# cpld_EPM3256_v3.net
KiCad netlist of a schematic drawn in EAGLE
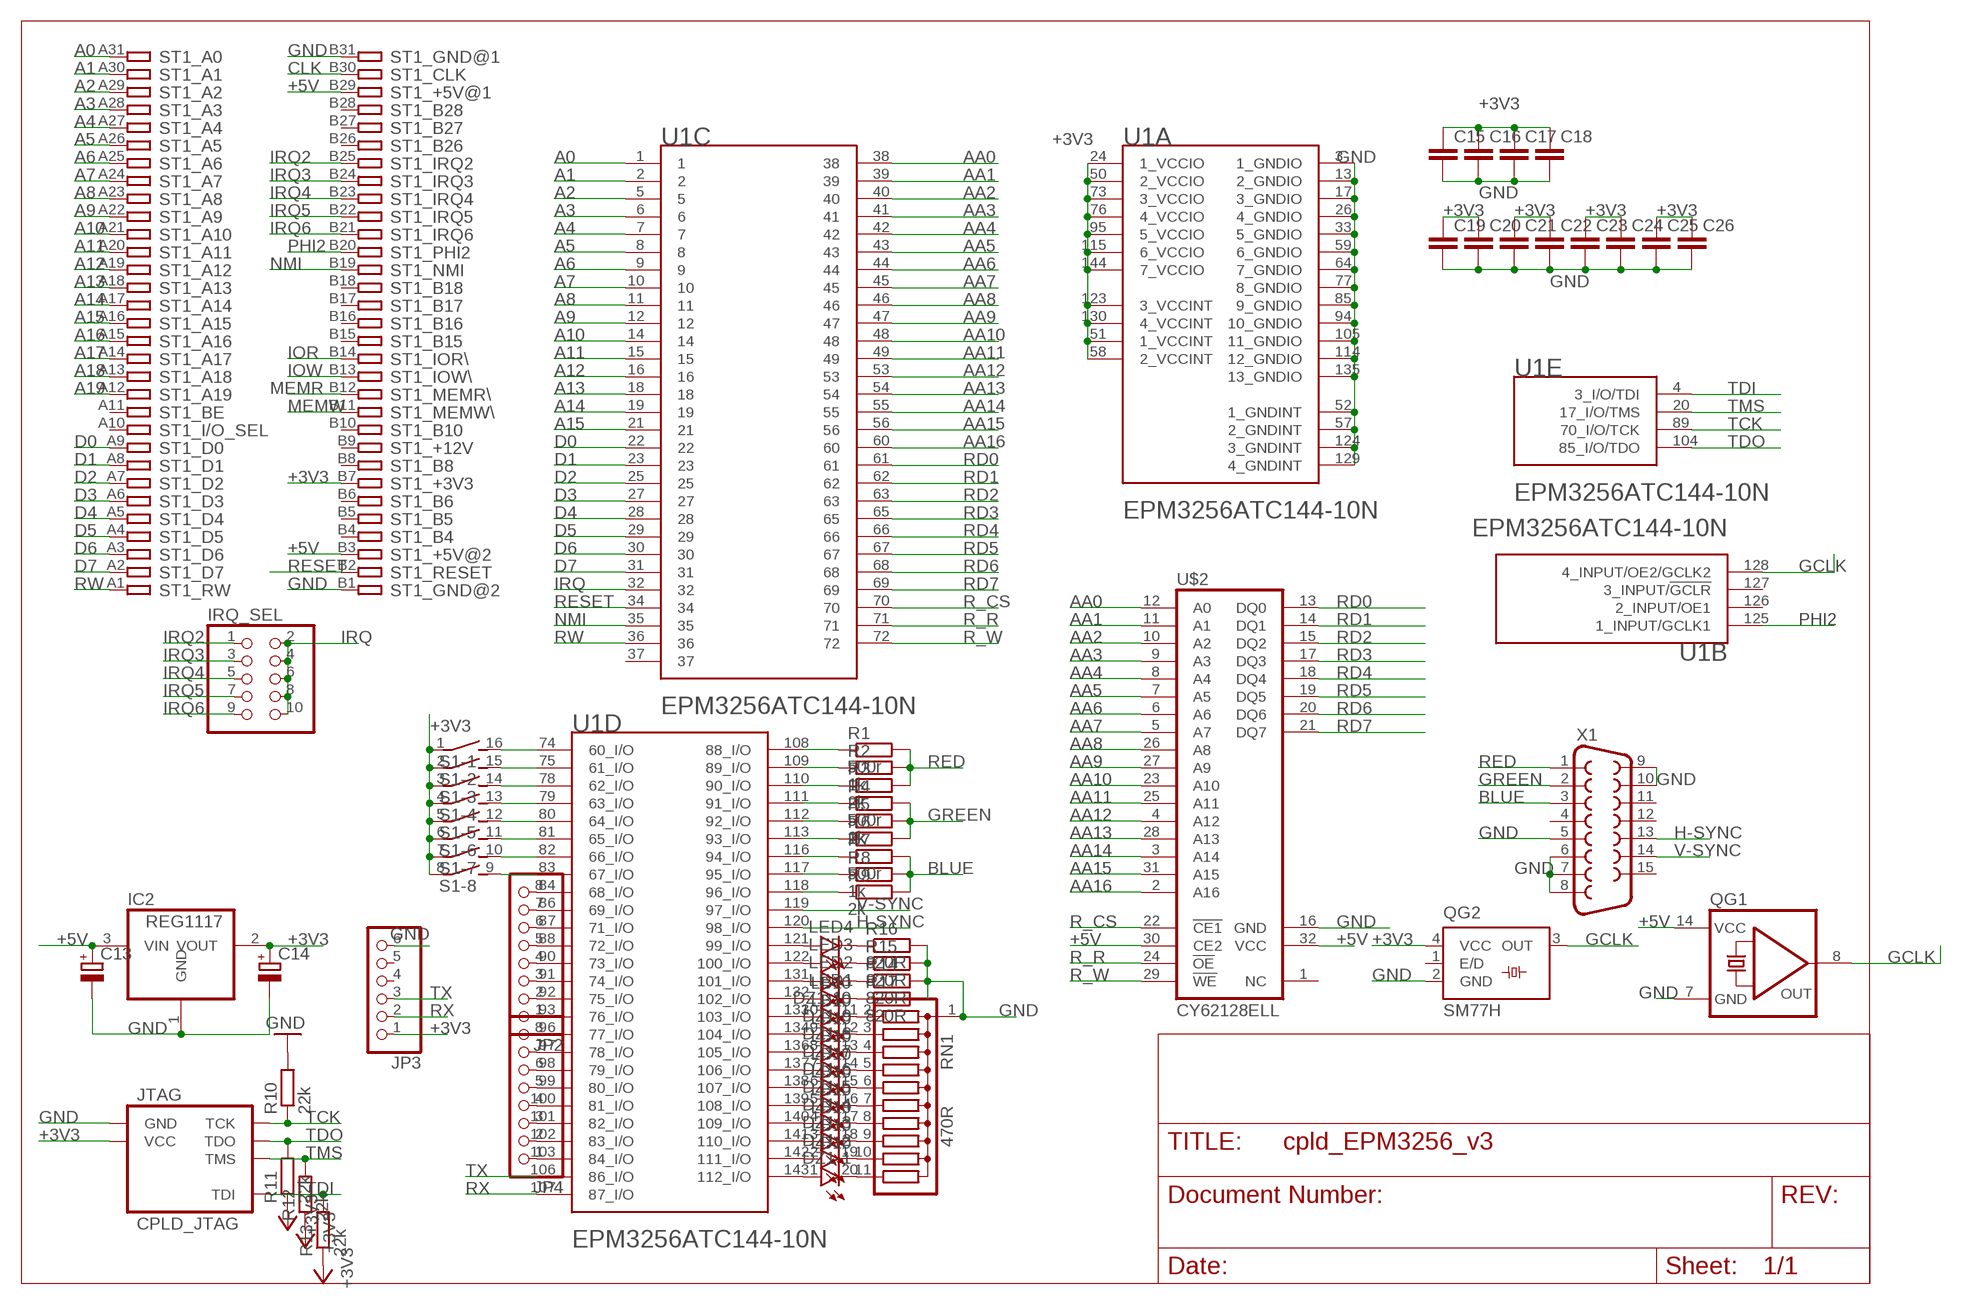
[diagram p0: schematic, sheet 1]

(export (version "E")
  (design (tool "Eeschema 10.0.6"))
  (components
    (comp (ref "C13")
      (value "CPOL-EUE2.5-5")
      (footprint "eagle-import:E2,5-5")
      (libsource (lib "eagle-import") (part "CPOL-EUE2.5-5"))
    )
    (comp (ref "C14")
      (value "CPOL-EUE2.5-5")
      (footprint "eagle-import:E2,5-5")
      (libsource (lib "eagle-import") (part "CPOL-EUE2.5-5"))
    )
    (comp (ref "C15")
      (value "C-EU050-035X075")
      (footprint "eagle-import:C050-035X075")
      (libsource (lib "eagle-import") (part "C-EU050-035X075"))
    )
    (comp (ref "C16")
      (value "C-EU050-035X075")
      (footprint "eagle-import:C050-035X075")
      (libsource (lib "eagle-import") (part "C-EU050-035X075"))
    )
    (comp (ref "C17")
      (value "C-EU050-035X075")
      (footprint "eagle-import:C050-035X075")
      (libsource (lib "eagle-import") (part "C-EU050-035X075"))
    )
    (comp (ref "C18")
      (value "C-EU050-035X075")
      (footprint "eagle-import:C050-035X075")
      (libsource (lib "eagle-import") (part "C-EU050-035X075"))
    )
    (comp (ref "C19")
      (value "C-EU050-035X075")
      (footprint "eagle-import:C050-035X075")
      (libsource (lib "eagle-import") (part "C-EU050-035X075"))
    )
    (comp (ref "C20")
      (value "C-EU050-035X075")
      (footprint "eagle-import:C050-035X075")
      (libsource (lib "eagle-import") (part "C-EU050-035X075"))
    )
    (comp (ref "C21")
      (value "C-EU050-035X075")
      (footprint "eagle-import:C050-035X075")
      (libsource (lib "eagle-import") (part "C-EU050-035X075"))
    )
    (comp (ref "C22")
      (value "C-EU050-035X075")
      (footprint "eagle-import:C050-035X075")
      (libsource (lib "eagle-import") (part "C-EU050-035X075"))
    )
    (comp (ref "C23")
      (value "C-EU050-035X075")
      (footprint "eagle-import:C050-035X075")
      (libsource (lib "eagle-import") (part "C-EU050-035X075"))
    )
    (comp (ref "C24")
      (value "C-EU050-035X075")
      (footprint "eagle-import:C050-035X075")
      (libsource (lib "eagle-import") (part "C-EU050-035X075"))
    )
    (comp (ref "C25")
      (value "C-EU050-035X075")
      (footprint "eagle-import:C050-035X075")
      (libsource (lib "eagle-import") (part "C-EU050-035X075"))
    )
    (comp (ref "C26")
      (value "C-EU050-035X075")
      (footprint "eagle-import:C050-035X075")
      (libsource (lib "eagle-import") (part "C-EU050-035X075"))
    )
    (comp (ref "DZ1")
      (value "LB10")
      (footprint "eagle-import:LB10")
      (libsource (lib "eagle-import") (part "LB10"))
    )
    (comp (ref "IC2")
      (value "REG1117")
      (footprint "eagle-import:SOT223")
      (libsource (lib "eagle-import") (part "REG1117"))
    )
    (comp (ref "IRQ_SEL")
      (value "PINHD-2X5")
      (footprint "eagle-import:2X05")
      (libsource (lib "eagle-import") (part "PINHD-2X5"))
    )
    (comp (ref "JP2")
      (value "PINHD-1X8")
      (footprint "eagle-import:1X08")
      (libsource (lib "eagle-import") (part "PINHD-1X8"))
    )
    (comp (ref "JP3")
      (value "PINHD-1X6/90")
      (footprint "eagle-import:1X06_90")
      (libsource (lib "eagle-import") (part "PINHD-1X6/90"))
    )
    (comp (ref "JP4")
      (value "PINHD-1X8")
      (footprint "eagle-import:1X08")
      (libsource (lib "eagle-import") (part "PINHD-1X8"))
    )
    (comp (ref "JTAG")
      (value "CPLD_JTAG")
      (footprint "eagle-import:2X05")
      (libsource (lib "eagle-import") (part "CPLD_JTAG"))
    )
    (comp (ref "LED1")
      (value "LED3MM")
      (footprint "eagle-import:LED3MM")
      (libsource (lib "eagle-import") (part "LED3MM"))
    )
    (comp (ref "LED2")
      (value "LED3MM")
      (footprint "eagle-import:LED3MM")
      (libsource (lib "eagle-import") (part "LED3MM"))
    )
    (comp (ref "LED3")
      (value "LED3MM")
      (footprint "eagle-import:LED3MM")
      (libsource (lib "eagle-import") (part "LED3MM"))
    )
    (comp (ref "LED4")
      (value "LED3MM")
      (footprint "eagle-import:LED3MM")
      (libsource (lib "eagle-import") (part "LED3MM"))
    )
    (comp (ref "QG1")
      (value "QG5860")
      (footprint "eagle-import:DIL14S")
      (libsource (lib "eagle-import") (part "QG5860"))
    )
    (comp (ref "QG2")
      (value "SM77H")
      (footprint "eagle-import:SM77H")
      (libsource (lib "eagle-import") (part "SM77H"))
    )
    (comp (ref "R1")
      (value "500r")
      (footprint "eagle-import:0204V")
      (libsource (lib "eagle-import") (part "R-EU_0204/2V"))
    )
    (comp (ref "R2")
      (value "1k")
      (footprint "eagle-import:0204V")
      (libsource (lib "eagle-import") (part "R-EU_0204/2V"))
    )
    (comp (ref "R3")
      (value "2k")
      (footprint "eagle-import:0204V")
      (libsource (lib "eagle-import") (part "R-EU_0204/2V"))
    )
    (comp (ref "R4")
      (value "500r")
      (footprint "eagle-import:0204V")
      (libsource (lib "eagle-import") (part "R-EU_0204/2V"))
    )
    (comp (ref "R5")
      (value "1k")
      (footprint "eagle-import:0204V")
      (libsource (lib "eagle-import") (part "R-EU_0204/2V"))
    )
    (comp (ref "R6")
      (value "2k")
      (footprint "eagle-import:0204V")
      (libsource (lib "eagle-import") (part "R-EU_0204/2V"))
    )
    (comp (ref "R7")
      (value "500r")
      (footprint "eagle-import:0204V")
      (libsource (lib "eagle-import") (part "R-EU_0204/2V"))
    )
    (comp (ref "R8")
      (value "1k")
      (footprint "eagle-import:0204V")
      (libsource (lib "eagle-import") (part "R-EU_0204/2V"))
    )
    (comp (ref "R9")
      (value "2k")
      (footprint "eagle-import:0204V")
      (libsource (lib "eagle-import") (part "R-EU_0204/2V"))
    )
    (comp (ref "R10")
      (value "22k")
      (footprint "eagle-import:0207_7")
      (libsource (lib "eagle-import") (part "R-EU_0207/7"))
    )
    (comp (ref "R11")
      (value "22k")
      (footprint "eagle-import:0207_7")
      (libsource (lib "eagle-import") (part "R-EU_0207/7"))
    )
    (comp (ref "R12")
      (value "22k")
      (footprint "eagle-import:0207_7")
      (libsource (lib "eagle-import") (part "R-EU_0207/7"))
    )
    (comp (ref "R13")
      (value "22k")
      (footprint "eagle-import:0207_7")
      (libsource (lib "eagle-import") (part "R-EU_0207/7"))
    )
    (comp (ref "R14")
      (value "820R")
      (footprint "eagle-import:0207_2V")
      (libsource (lib "eagle-import") (part "R-EU_0207/2V"))
    )
    (comp (ref "R15")
      (value "820R")
      (footprint "eagle-import:0207_2V")
      (libsource (lib "eagle-import") (part "R-EU_0207/2V"))
    )
    (comp (ref "R16")
      (value "820R")
      (footprint "eagle-import:0207_2V")
      (libsource (lib "eagle-import") (part "R-EU_0207/2V"))
    )
    (comp (ref "R17")
      (value "820R")
      (footprint "eagle-import:0207_2V")
      (libsource (lib "eagle-import") (part "R-EU_0207/2V"))
    )
    (comp (ref "RN1")
      (value "470R")
      (footprint "eagle-import:SIL11")
      (libsource (lib "eagle-import") (part "G10R"))
    )
    (comp (ref "S1")
      (value "DIP08S")
      (footprint "eagle-import:DIP08S")
      (libsource (lib "eagle-import") (part "DIP08S"))
    )
    (comp (ref "ST1")
      (value "IBM8BIT_ISA")
      (footprint "eagle-import:IBM8BIT")
      (libsource (lib "eagle-import") (part "IBM8BIT_ISA"))
    )
    (comp (ref "U$2")
      (value "CY62128ELL")
      (footprint "eagle-import:SOIC32")
      (libsource (lib "eagle-import") (part "CY62128ELL"))
    )
    (comp (ref "U1")
      (value "EPM3256ATC144")
      (footprint "eagle-import:TQFP144-BB")
      (libsource (lib "eagle-import") (part "EPM3256ATC144"))
    )
    (comp (ref "X1")
      (value "F15HDH")
      (footprint "eagle-import:HDF15H")
      (libsource (lib "eagle-import") (part "F15HDH"))
    )
  )
  (nets
    (net (code "1") (name "+3V3") (class "Default")
      (node (ref "C14") (pin "+") (pinfunction "+_+") (pintype "passive"))
      (node (ref "C15") (pin "1") (pinfunction "1_1") (pintype "passive"))
      (node (ref "C16") (pin "1") (pinfunction "1_1") (pintype "passive"))
      (node (ref "C17") (pin "1") (pinfunction "1_1") (pintype "passive"))
      (node (ref "C18") (pin "1") (pinfunction "1_1") (pintype "passive"))
      (node (ref "C19") (pin "1") (pinfunction "1_1") (pintype "passive"))
      (node (ref "C20") (pin "1") (pinfunction "1_1") (pintype "passive"))
      (node (ref "C21") (pin "1") (pinfunction "1_1") (pintype "passive"))
      (node (ref "C22") (pin "1") (pinfunction "1_1") (pintype "passive"))
      (node (ref "C23") (pin "1") (pinfunction "1_1") (pintype "passive"))
      (node (ref "C24") (pin "1") (pinfunction "1_1") (pintype "passive"))
      (node (ref "C25") (pin "1") (pinfunction "1_1") (pintype "passive"))
      (node (ref "C26") (pin "1") (pinfunction "1_1") (pintype "passive"))
      (node (ref "IC2") (pin "2") (pinfunction "VOUT_2") (pintype "output"))
      (node (ref "JP3") (pin "1") (pinfunction "1_1") (pintype "passive"))
      (node (ref "JTAG") (pin "4") (pinfunction "VCC_4") (pintype "power_in"))
      (node (ref "QG2") (pin "4") (pinfunction "VCC_4") (pintype "power_in"))
      (node (ref "R11") (pin "1") (pinfunction "1_1") (pintype "passive"))
      (node (ref "R12") (pin "1") (pinfunction "1_1") (pintype "passive"))
      (node (ref "R13") (pin "1") (pinfunction "1_1") (pintype "passive"))
      (node (ref "S1") (pin "1") (pinfunction "1_1") (pintype "passive"))
      (node (ref "S1") (pin "2") (pinfunction "1_2") (pintype "passive"))
      (node (ref "S1") (pin "3") (pinfunction "1_3") (pintype "passive"))
      (node (ref "S1") (pin "4") (pinfunction "1_4") (pintype "passive"))
      (node (ref "S1") (pin "5") (pinfunction "1_5") (pintype "passive"))
      (node (ref "S1") (pin "6") (pinfunction "1_6") (pintype "passive"))
      (node (ref "S1") (pin "7") (pinfunction "1_7") (pintype "passive"))
      (node (ref "S1") (pin "8") (pinfunction "1_8") (pintype "passive"))
      (node (ref "ST1") (pin "B7") (pinfunction "P_B7") (pintype "bidirectional"))
      (node (ref "U1") (pin "115") (pinfunction "6_VCCIO_115") (pintype "power_in"))
      (node (ref "U1") (pin "123") (pinfunction "3_VCCINT_123") (pintype "power_in"))
      (node (ref "U1") (pin "130") (pinfunction "4_VCCINT_130") (pintype "power_in"))
      (node (ref "U1") (pin "144") (pinfunction "7_VCCIO_144") (pintype "power_in"))
      (node (ref "U1") (pin "24") (pinfunction "1_VCCIO_24") (pintype "power_in"))
      (node (ref "U1") (pin "50") (pinfunction "2_VCCIO_50") (pintype "power_in"))
      (node (ref "U1") (pin "51") (pinfunction "1_VCCINT_51") (pintype "power_in"))
      (node (ref "U1") (pin "58") (pinfunction "2_VCCINT_58") (pintype "power_in"))
      (node (ref "U1") (pin "73") (pinfunction "3_VCCIO_73") (pintype "power_in"))
      (node (ref "U1") (pin "76") (pinfunction "4_VCCIO_76") (pintype "power_in"))
      (node (ref "U1") (pin "95") (pinfunction "5_VCCIO_95") (pintype "power_in"))
    )
    (net (code "2") (name "/+5V") (class "Default")
      (node (ref "C13") (pin "+") (pinfunction "+_+") (pintype "passive"))
      (node (ref "IC2") (pin "3") (pinfunction "VIN_3") (pintype "input"))
      (node (ref "QG1") (pin "14") (pinfunction "VCC_14") (pintype "power_in"))
      (node (ref "ST1") (pin "B29") (pinfunction "P_B29") (pintype "bidirectional"))
      (node (ref "ST1") (pin "B3") (pinfunction "P_B3") (pintype "bidirectional"))
      (node (ref "U$2") (pin "30") (pinfunction "CE2_30") (pintype "input"))
      (node (ref "U$2") (pin "32") (pinfunction "VCC_32") (pintype "bidirectional"))
    )
    (net (code "3") (name "/A0") (class "Default")
      (node (ref "ST1") (pin "A31") (pinfunction "P_A31") (pintype "bidirectional"))
      (node (ref "U1") (pin "1") (pinfunction "1_1") (pintype "bidirectional"))
    )
    (net (code "4") (name "/A1") (class "Default")
      (node (ref "ST1") (pin "A30") (pinfunction "P_A30") (pintype "bidirectional"))
      (node (ref "U1") (pin "2") (pinfunction "2_2") (pintype "bidirectional"))
    )
    (net (code "5") (name "/A2") (class "Default")
      (node (ref "ST1") (pin "A29") (pinfunction "P_A29") (pintype "bidirectional"))
      (node (ref "U1") (pin "5") (pinfunction "5_5") (pintype "bidirectional"))
    )
    (net (code "6") (name "/A3") (class "Default")
      (node (ref "ST1") (pin "A28") (pinfunction "P_A28") (pintype "bidirectional"))
      (node (ref "U1") (pin "6") (pinfunction "6_6") (pintype "bidirectional"))
    )
    (net (code "7") (name "/A4") (class "Default")
      (node (ref "ST1") (pin "A27") (pinfunction "P_A27") (pintype "bidirectional"))
      (node (ref "U1") (pin "7") (pinfunction "7_7") (pintype "bidirectional"))
    )
    (net (code "8") (name "/A5") (class "Default")
      (node (ref "ST1") (pin "A26") (pinfunction "P_A26") (pintype "bidirectional"))
      (node (ref "U1") (pin "8") (pinfunction "8_8") (pintype "bidirectional"))
    )
    (net (code "9") (name "/A6") (class "Default")
      (node (ref "ST1") (pin "A25") (pinfunction "P_A25") (pintype "bidirectional"))
      (node (ref "U1") (pin "9") (pinfunction "9_9") (pintype "bidirectional"))
    )
    (net (code "10") (name "/A7") (class "Default")
      (node (ref "ST1") (pin "A24") (pinfunction "P_A24") (pintype "bidirectional"))
      (node (ref "U1") (pin "10") (pinfunction "10_10") (pintype "bidirectional"))
    )
    (net (code "11") (name "/A8") (class "Default")
      (node (ref "ST1") (pin "A23") (pinfunction "P_A23") (pintype "bidirectional"))
      (node (ref "U1") (pin "11") (pinfunction "11_11") (pintype "bidirectional"))
    )
    (net (code "12") (name "/A9") (class "Default")
      (node (ref "ST1") (pin "A22") (pinfunction "P_A22") (pintype "bidirectional"))
      (node (ref "U1") (pin "12") (pinfunction "12_12") (pintype "bidirectional"))
    )
    (net (code "13") (name "/A10") (class "Default")
      (node (ref "ST1") (pin "A21") (pinfunction "P_A21") (pintype "bidirectional"))
      (node (ref "U1") (pin "14") (pinfunction "14_14") (pintype "bidirectional"))
    )
    (net (code "14") (name "/A11") (class "Default")
      (node (ref "ST1") (pin "A20") (pinfunction "P_A20") (pintype "bidirectional"))
      (node (ref "U1") (pin "15") (pinfunction "15_15") (pintype "bidirectional"))
    )
    (net (code "15") (name "/A12") (class "Default")
      (node (ref "ST1") (pin "A19") (pinfunction "P_A19") (pintype "bidirectional"))
      (node (ref "U1") (pin "16") (pinfunction "16_16") (pintype "bidirectional"))
    )
    (net (code "16") (name "/A13") (class "Default")
      (node (ref "ST1") (pin "A18") (pinfunction "P_A18") (pintype "bidirectional"))
      (node (ref "U1") (pin "18") (pinfunction "18_18") (pintype "bidirectional"))
    )
    (net (code "17") (name "/A14") (class "Default")
      (node (ref "ST1") (pin "A17") (pinfunction "P_A17") (pintype "bidirectional"))
      (node (ref "U1") (pin "19") (pinfunction "19_19") (pintype "bidirectional"))
    )
    (net (code "18") (name "/A15") (class "Default")
      (node (ref "ST1") (pin "A16") (pinfunction "P_A16") (pintype "bidirectional"))
      (node (ref "U1") (pin "21") (pinfunction "21_21") (pintype "bidirectional"))
    )
    (net (code "19") (name "/A16") (class "Default")
      (node (ref "ST1") (pin "A15") (pinfunction "P_A15") (pintype "bidirectional"))
    )
    (net (code "20") (name "/A17") (class "Default")
      (node (ref "ST1") (pin "A14") (pinfunction "P_A14") (pintype "bidirectional"))
    )
    (net (code "21") (name "/A18") (class "Default")
      (node (ref "ST1") (pin "A13") (pinfunction "P_A13") (pintype "bidirectional"))
    )
    (net (code "22") (name "/A19") (class "Default")
      (node (ref "ST1") (pin "A12") (pinfunction "P_A12") (pintype "bidirectional"))
    )
    (net (code "23") (name "/AA0") (class "Default")
      (node (ref "U$2") (pin "12") (pinfunction "A0_12") (pintype "input"))
      (node (ref "U1") (pin "38") (pinfunction "38_38") (pintype "bidirectional"))
    )
    (net (code "24") (name "/AA1") (class "Default")
      (node (ref "U$2") (pin "11") (pinfunction "A1_11") (pintype "input"))
      (node (ref "U1") (pin "39") (pinfunction "39_39") (pintype "bidirectional"))
    )
    (net (code "25") (name "/AA2") (class "Default")
      (node (ref "U$2") (pin "10") (pinfunction "A2_10") (pintype "input"))
      (node (ref "U1") (pin "40") (pinfunction "40_40") (pintype "bidirectional"))
    )
    (net (code "26") (name "/AA3") (class "Default")
      (node (ref "U$2") (pin "9") (pinfunction "A3_9") (pintype "input"))
      (node (ref "U1") (pin "41") (pinfunction "41_41") (pintype "bidirectional"))
    )
    (net (code "27") (name "/AA4") (class "Default")
      (node (ref "U$2") (pin "8") (pinfunction "A4_8") (pintype "input"))
      (node (ref "U1") (pin "42") (pinfunction "42_42") (pintype "bidirectional"))
    )
    (net (code "28") (name "/AA5") (class "Default")
      (node (ref "U$2") (pin "7") (pinfunction "A5_7") (pintype "input"))
      (node (ref "U1") (pin "43") (pinfunction "43_43") (pintype "bidirectional"))
    )
    (net (code "29") (name "/AA6") (class "Default")
      (node (ref "U$2") (pin "6") (pinfunction "A6_6") (pintype "input"))
      (node (ref "U1") (pin "44") (pinfunction "44_44") (pintype "bidirectional"))
    )
    (net (code "30") (name "/AA7") (class "Default")
      (node (ref "U$2") (pin "5") (pinfunction "A7_5") (pintype "input"))
      (node (ref "U1") (pin "45") (pinfunction "45_45") (pintype "bidirectional"))
    )
    (net (code "31") (name "/AA8") (class "Default")
      (node (ref "U$2") (pin "26") (pinfunction "A8_26") (pintype "input"))
      (node (ref "U1") (pin "46") (pinfunction "46_46") (pintype "bidirectional"))
    )
    (net (code "32") (name "/AA9") (class "Default")
      (node (ref "U$2") (pin "27") (pinfunction "A9_27") (pintype "input"))
      (node (ref "U1") (pin "47") (pinfunction "47_47") (pintype "bidirectional"))
    )
    (net (code "33") (name "/AA10") (class "Default")
      (node (ref "U$2") (pin "23") (pinfunction "A10_23") (pintype "input"))
      (node (ref "U1") (pin "48") (pinfunction "48_48") (pintype "bidirectional"))
    )
    (net (code "34") (name "/AA11") (class "Default")
      (node (ref "U$2") (pin "25") (pinfunction "A11_25") (pintype "input"))
      (node (ref "U1") (pin "49") (pinfunction "49_49") (pintype "bidirectional"))
    )
    (net (code "35") (name "/AA12") (class "Default")
      (node (ref "U$2") (pin "4") (pinfunction "A12_4") (pintype "input"))
      (node (ref "U1") (pin "53") (pinfunction "53_53") (pintype "bidirectional"))
    )
    (net (code "36") (name "/AA13") (class "Default")
      (node (ref "U$2") (pin "28") (pinfunction "A13_28") (pintype "input"))
      (node (ref "U1") (pin "54") (pinfunction "54_54") (pintype "bidirectional"))
    )
    (net (code "37") (name "/AA14") (class "Default")
      (node (ref "U$2") (pin "3") (pinfunction "A14_3") (pintype "input"))
      (node (ref "U1") (pin "55") (pinfunction "55_55") (pintype "bidirectional"))
    )
    (net (code "38") (name "/AA15") (class "Default")
      (node (ref "U$2") (pin "31") (pinfunction "A15_31") (pintype "input"))
      (node (ref "U1") (pin "56") (pinfunction "56_56") (pintype "bidirectional"))
    )
    (net (code "39") (name "/AA16") (class "Default")
      (node (ref "U$2") (pin "2") (pinfunction "A16_2") (pintype "input"))
      (node (ref "U1") (pin "60") (pinfunction "60_60") (pintype "bidirectional"))
    )
    (net (code "40") (name "/BLUE") (class "Default")
      (node (ref "R7") (pin "2") (pinfunction "2_2") (pintype "passive"))
      (node (ref "R8") (pin "2") (pinfunction "2_2") (pintype "passive"))
      (node (ref "R9") (pin "2") (pinfunction "2_2") (pintype "passive"))
      (node (ref "X1") (pin "3") (pinfunction "3_3") (pintype "passive"))
    )
    (net (code "41") (name "/CLK") (class "Default")
      (node (ref "ST1") (pin "B30") (pinfunction "P_B30") (pintype "bidirectional"))
    )
    (net (code "42") (name "/D0") (class "Default")
      (node (ref "ST1") (pin "A9") (pinfunction "P_A9") (pintype "bidirectional"))
      (node (ref "U1") (pin "22") (pinfunction "22_22") (pintype "bidirectional"))
    )
    (net (code "43") (name "/D1") (class "Default")
      (node (ref "ST1") (pin "A8") (pinfunction "P_A8") (pintype "bidirectional"))
      (node (ref "U1") (pin "23") (pinfunction "23_23") (pintype "bidirectional"))
    )
    (net (code "44") (name "/D2") (class "Default")
      (node (ref "ST1") (pin "A7") (pinfunction "P_A7") (pintype "bidirectional"))
      (node (ref "U1") (pin "25") (pinfunction "25_25") (pintype "bidirectional"))
    )
    (net (code "45") (name "/D3") (class "Default")
      (node (ref "ST1") (pin "A6") (pinfunction "P_A6") (pintype "bidirectional"))
      (node (ref "U1") (pin "27") (pinfunction "27_27") (pintype "bidirectional"))
    )
    (net (code "46") (name "/D4") (class "Default")
      (node (ref "ST1") (pin "A5") (pinfunction "P_A5") (pintype "bidirectional"))
      (node (ref "U1") (pin "28") (pinfunction "28_28") (pintype "bidirectional"))
    )
    (net (code "47") (name "/D5") (class "Default")
      (node (ref "ST1") (pin "A4") (pinfunction "P_A4") (pintype "bidirectional"))
      (node (ref "U1") (pin "29") (pinfunction "29_29") (pintype "bidirectional"))
    )
    (net (code "48") (name "/D6") (class "Default")
      (node (ref "ST1") (pin "A3") (pinfunction "P_A3") (pintype "bidirectional"))
      (node (ref "U1") (pin "30") (pinfunction "30_30") (pintype "bidirectional"))
    )
    (net (code "49") (name "/D7") (class "Default")
      (node (ref "ST1") (pin "A2") (pinfunction "P_A2") (pintype "bidirectional"))
      (node (ref "U1") (pin "31") (pinfunction "31_31") (pintype "bidirectional"))
    )
    (net (code "50") (name "/GCLK") (class "Default")
      (node (ref "QG1") (pin "8") (pinfunction "OUT_8") (pintype "output"))
      (node (ref "QG2") (pin "3") (pinfunction "OUT_3") (pintype "output"))
      (node (ref "U1") (pin "128") (pinfunction "4_INPUT/OE2/GCLK2_128") (pintype "input"))
    )
    (net (code "51") (name "/GREEN") (class "Default")
      (node (ref "R4") (pin "2") (pinfunction "2_2") (pintype "passive"))
      (node (ref "R5") (pin "2") (pinfunction "2_2") (pintype "passive"))
      (node (ref "R6") (pin "2") (pinfunction "2_2") (pintype "passive"))
      (node (ref "X1") (pin "2") (pinfunction "2_2") (pintype "passive"))
    )
    (net (code "52") (name "/H-SYNC") (class "Default")
      (node (ref "U1") (pin "120") (pinfunction "98_I/O_120") (pintype "bidirectional"))
      (node (ref "X1") (pin "13") (pinfunction "13_13") (pintype "passive"))
    )
    (net (code "53") (name "/IOR") (class "Default")
      (node (ref "ST1") (pin "B14") (pinfunction "P_B14") (pintype "bidirectional"))
    )
    (net (code "54") (name "/IOW") (class "Default")
      (node (ref "ST1") (pin "B13") (pinfunction "P_B13") (pintype "bidirectional"))
    )
    (net (code "55") (name "/IRQ") (class "Default")
      (node (ref "IRQ_SEL") (pin "10") (pinfunction "10_10") (pintype "passive"))
      (node (ref "IRQ_SEL") (pin "2") (pinfunction "2_2") (pintype "passive"))
      (node (ref "IRQ_SEL") (pin "4") (pinfunction "4_4") (pintype "passive"))
      (node (ref "IRQ_SEL") (pin "6") (pinfunction "6_6") (pintype "passive"))
      (node (ref "IRQ_SEL") (pin "8") (pinfunction "8_8") (pintype "passive"))
      (node (ref "U1") (pin "32") (pinfunction "32_32") (pintype "bidirectional"))
    )
    (net (code "56") (name "/IRQ2") (class "Default")
      (node (ref "IRQ_SEL") (pin "1") (pinfunction "1_1") (pintype "passive"))
      (node (ref "ST1") (pin "B25") (pinfunction "P_B25") (pintype "bidirectional"))
    )
    (net (code "57") (name "/IRQ3") (class "Default")
      (node (ref "IRQ_SEL") (pin "3") (pinfunction "3_3") (pintype "passive"))
      (node (ref "ST1") (pin "B24") (pinfunction "P_B24") (pintype "bidirectional"))
    )
    (net (code "58") (name "/IRQ4") (class "Default")
      (node (ref "IRQ_SEL") (pin "5") (pinfunction "5_5") (pintype "passive"))
      (node (ref "ST1") (pin "B23") (pinfunction "P_B23") (pintype "bidirectional"))
    )
    (net (code "59") (name "/IRQ5") (class "Default")
      (node (ref "IRQ_SEL") (pin "7") (pinfunction "7_7") (pintype "passive"))
      (node (ref "ST1") (pin "B22") (pinfunction "P_B22") (pintype "bidirectional"))
    )
    (net (code "60") (name "/IRQ6") (class "Default")
      (node (ref "IRQ_SEL") (pin "9") (pinfunction "9_9") (pintype "passive"))
      (node (ref "ST1") (pin "B21") (pinfunction "P_B21") (pintype "bidirectional"))
    )
    (net (code "61") (name "/MEMR") (class "Default")
      (node (ref "ST1") (pin "B12") (pinfunction "P_B12") (pintype "bidirectional"))
    )
    (net (code "62") (name "/MEMW") (class "Default")
      (node (ref "ST1") (pin "B11") (pinfunction "P_B11") (pintype "bidirectional"))
    )
    (net (code "63") (name "/NMI") (class "Default")
      (node (ref "ST1") (pin "B19") (pinfunction "P_B19") (pintype "bidirectional"))
      (node (ref "U1") (pin "35") (pinfunction "35_35") (pintype "bidirectional"))
    )
    (net (code "64") (name "/PHI2") (class "Default")
      (node (ref "ST1") (pin "B20") (pinfunction "P_B20") (pintype "bidirectional"))
      (node (ref "U1") (pin "125") (pinfunction "1_INPUT/GCLK1_125") (pintype "input"))
    )
    (net (code "65") (name "/RD0") (class "Default")
      (node (ref "U$2") (pin "13") (pinfunction "DQ0_13") (pintype "bidirectional"))
      (node (ref "U1") (pin "61") (pinfunction "61_61") (pintype "bidirectional"))
    )
    (net (code "66") (name "/RD1") (class "Default")
      (node (ref "U$2") (pin "14") (pinfunction "DQ1_14") (pintype "bidirectional"))
      (node (ref "U1") (pin "62") (pinfunction "62_62") (pintype "bidirectional"))
    )
    (net (code "67") (name "/RD2") (class "Default")
      (node (ref "U$2") (pin "15") (pinfunction "DQ2_15") (pintype "bidirectional"))
      (node (ref "U1") (pin "63") (pinfunction "63_63") (pintype "bidirectional"))
    )
    (net (code "68") (name "/RD3") (class "Default")
      (node (ref "U$2") (pin "17") (pinfunction "DQ3_17") (pintype "bidirectional"))
      (node (ref "U1") (pin "65") (pinfunction "65_65") (pintype "bidirectional"))
    )
    (net (code "69") (name "/RD4") (class "Default")
      (node (ref "U$2") (pin "18") (pinfunction "DQ4_18") (pintype "bidirectional"))
      (node (ref "U1") (pin "66") (pinfunction "66_66") (pintype "bidirectional"))
    )
    (net (code "70") (name "/RD5") (class "Default")
      (node (ref "U$2") (pin "19") (pinfunction "DQ5_19") (pintype "bidirectional"))
      (node (ref "U1") (pin "67") (pinfunction "67_67") (pintype "bidirectional"))
    )
    (net (code "71") (name "/RD6") (class "Default")
      (node (ref "U$2") (pin "20") (pinfunction "DQ6_20") (pintype "bidirectional"))
      (node (ref "U1") (pin "68") (pinfunction "68_68") (pintype "bidirectional"))
    )
    (net (code "72") (name "/RD7") (class "Default")
      (node (ref "U$2") (pin "21") (pinfunction "DQ7_21") (pintype "bidirectional"))
      (node (ref "U1") (pin "69") (pinfunction "69_69") (pintype "bidirectional"))
    )
    (net (code "73") (name "/RED") (class "Default")
      (node (ref "R1") (pin "2") (pinfunction "2_2") (pintype "passive"))
      (node (ref "R2") (pin "2") (pinfunction "2_2") (pintype "passive"))
      (node (ref "R3") (pin "2") (pinfunction "2_2") (pintype "passive"))
      (node (ref "X1") (pin "1") (pinfunction "1_1") (pintype "passive"))
    )
    (net (code "74") (name "/RESET") (class "Default")
      (node (ref "ST1") (pin "B2") (pinfunction "P_B2") (pintype "bidirectional"))
      (node (ref "U1") (pin "34") (pinfunction "34_34") (pintype "bidirectional"))
    )
    (net (code "75") (name "/RW") (class "Default")
      (node (ref "ST1") (pin "A1") (pinfunction "P_A1") (pintype "bidirectional"))
      (node (ref "U1") (pin "36") (pinfunction "36_36") (pintype "bidirectional"))
    )
    (net (code "76") (name "/RX") (class "Default")
      (node (ref "JP3") (pin "2") (pinfunction "2_2") (pintype "passive"))
      (node (ref "U1") (pin "107") (pinfunction "87_I/O_107") (pintype "bidirectional"))
    )
    (net (code "77") (name "/R_CS") (class "Default")
      (node (ref "U$2") (pin "22") (pinfunction "~{CE1}_22") (pintype "input"))
      (node (ref "U1") (pin "70") (pinfunction "70_70") (pintype "bidirectional"))
    )
    (net (code "78") (name "/R_R") (class "Default")
      (node (ref "U$2") (pin "24") (pinfunction "~{OE}_24") (pintype "input"))
      (node (ref "U1") (pin "71") (pinfunction "71_71") (pintype "bidirectional"))
    )
    (net (code "79") (name "/R_W") (class "Default")
      (node (ref "U$2") (pin "29") (pinfunction "~{WE}_29") (pintype "input"))
      (node (ref "U1") (pin "72") (pinfunction "72_72") (pintype "bidirectional"))
    )
    (net (code "80") (name "/TCK") (class "Default")
      (node (ref "JTAG") (pin "1") (pinfunction "TCK_1") (pintype "bidirectional"))
      (node (ref "R10") (pin "1") (pinfunction "1_1") (pintype "passive"))
      (node (ref "U1") (pin "89") (pinfunction "70_I/O/TCK_89") (pintype "bidirectional"))
    )
    (net (code "81") (name "/TDI") (class "Default")
      (node (ref "JTAG") (pin "9") (pinfunction "TDI_9") (pintype "bidirectional"))
      (node (ref "R13") (pin "2") (pinfunction "2_2") (pintype "passive"))
      (node (ref "U1") (pin "4") (pinfunction "3_I/O/TDI_4") (pintype "bidirectional"))
    )
    (net (code "82") (name "/TDO") (class "Default")
      (node (ref "JTAG") (pin "3") (pinfunction "TDO_3") (pintype "bidirectional"))
      (node (ref "R11") (pin "2") (pinfunction "2_2") (pintype "passive"))
      (node (ref "U1") (pin "104") (pinfunction "85_I/O/TDO_104") (pintype "bidirectional"))
    )
    (net (code "83") (name "/TMS") (class "Default")
      (node (ref "JTAG") (pin "5") (pinfunction "TMS_5") (pintype "bidirectional"))
      (node (ref "R12") (pin "2") (pinfunction "2_2") (pintype "passive"))
      (node (ref "U1") (pin "20") (pinfunction "17_I/O/TMS_20") (pintype "bidirectional"))
    )
    (net (code "84") (name "/TX") (class "Default")
      (node (ref "JP3") (pin "3") (pinfunction "3_3") (pintype "passive"))
      (node (ref "U1") (pin "106") (pinfunction "86_I/O_106") (pintype "bidirectional"))
    )
    (net (code "85") (name "/V-SYNC") (class "Default")
      (node (ref "U1") (pin "119") (pinfunction "97_I/O_119") (pintype "bidirectional"))
      (node (ref "X1") (pin "14") (pinfunction "14_14") (pintype "passive"))
    )
    (net (code "86") (name "GND") (class "Default")
      (node (ref "C13") (pin "-") (pinfunction "-_-") (pintype "passive"))
      (node (ref "C14") (pin "-") (pinfunction "-_-") (pintype "passive"))
      (node (ref "C15") (pin "2") (pinfunction "2_2") (pintype "passive"))
      (node (ref "C16") (pin "2") (pinfunction "2_2") (pintype "passive"))
      (node (ref "C17") (pin "2") (pinfunction "2_2") (pintype "passive"))
      (node (ref "C18") (pin "2") (pinfunction "2_2") (pintype "passive"))
      (node (ref "C19") (pin "2") (pinfunction "2_2") (pintype "passive"))
      (node (ref "C20") (pin "2") (pinfunction "2_2") (pintype "passive"))
      (node (ref "C21") (pin "2") (pinfunction "2_2") (pintype "passive"))
      (node (ref "C22") (pin "2") (pinfunction "2_2") (pintype "passive"))
      (node (ref "C23") (pin "2") (pinfunction "2_2") (pintype "passive"))
      (node (ref "C24") (pin "2") (pinfunction "2_2") (pintype "passive"))
      (node (ref "C25") (pin "2") (pinfunction "2_2") (pintype "passive"))
      (node (ref "C26") (pin "2") (pinfunction "2_2") (pintype "passive"))
      (node (ref "IC2") (pin "1") (pinfunction "GND_1") (pintype "power_in"))
      (node (ref "JP3") (pin "6") (pinfunction "6_6") (pintype "passive"))
      (node (ref "JTAG") (pin "10") (pinfunction "GND_10") (pintype "power_in"))
      (node (ref "JTAG") (pin "2") (pinfunction "GND_2") (pintype "power_in"))
      (node (ref "JTAG") (pin "6") (pinfunction "GND_6") (pintype "power_in"))
      (node (ref "JTAG") (pin "7") (pinfunction "GND_7") (pintype "power_in"))
      (node (ref "JTAG") (pin "8") (pinfunction "GND_8") (pintype "power_in"))
      (node (ref "QG1") (pin "7") (pinfunction "GND_7") (pintype "power_in"))
      (node (ref "QG2") (pin "2") (pinfunction "GND_2") (pintype "power_in"))
      (node (ref "R10") (pin "2") (pinfunction "2_2") (pintype "passive"))
      (node (ref "R14") (pin "2") (pinfunction "2_2") (pintype "passive"))
      (node (ref "R15") (pin "2") (pinfunction "2_2") (pintype "passive"))
      (node (ref "R16") (pin "2") (pinfunction "2_2") (pintype "passive"))
      (node (ref "R17") (pin "2") (pinfunction "2_2") (pintype "passive"))
      (node (ref "RN1") (pin "1") (pinfunction "1_1") (pintype "passive"))
      (node (ref "ST1") (pin "B1") (pinfunction "P_B1") (pintype "bidirectional"))
      (node (ref "ST1") (pin "B31") (pinfunction "P_B31") (pintype "bidirectional"))
      (node (ref "U$2") (pin "16") (pinfunction "GND_16") (pintype "bidirectional"))
      (node (ref "U1") (pin "105") (pinfunction "11_GNDIO_105") (pintype "power_in"))
      (node (ref "U1") (pin "114") (pinfunction "12_GNDIO_114") (pintype "power_in"))
      (node (ref "U1") (pin "124") (pinfunction "3_GNDINT_124") (pintype "power_in"))
      (node (ref "U1") (pin "129") (pinfunction "4_GNDINT_129") (pintype "power_in"))
      (node (ref "U1") (pin "13") (pinfunction "2_GNDIO_13") (pintype "power_in"))
      (node (ref "U1") (pin "135") (pinfunction "13_GNDIO_135") (pintype "power_in"))
      (node (ref "U1") (pin "17") (pinfunction "3_GNDIO_17") (pintype "power_in"))
      (node (ref "U1") (pin "26") (pinfunction "4_GNDIO_26") (pintype "power_in"))
      (node (ref "U1") (pin "3") (pinfunction "1_GNDIO_3") (pintype "power_in"))
      (node (ref "U1") (pin "33") (pinfunction "5_GNDIO_33") (pintype "power_in"))
      (node (ref "U1") (pin "52") (pinfunction "1_GNDINT_52") (pintype "power_in"))
      (node (ref "U1") (pin "57") (pinfunction "2_GNDINT_57") (pintype "power_in"))
      (node (ref "U1") (pin "59") (pinfunction "6_GNDIO_59") (pintype "power_in"))
      (node (ref "U1") (pin "64") (pinfunction "7_GNDIO_64") (pintype "power_in"))
      (node (ref "U1") (pin "77") (pinfunction "8_GNDIO_77") (pintype "power_in"))
      (node (ref "U1") (pin "85") (pinfunction "9_GNDIO_85") (pintype "power_in"))
      (node (ref "U1") (pin "94") (pinfunction "10_GNDIO_94") (pintype "power_in"))
      (node (ref "X1") (pin "10") (pinfunction "10_10") (pintype "passive"))
      (node (ref "X1") (pin "5") (pinfunction "5_5") (pintype "passive"))
      (node (ref "X1") (pin "6") (pinfunction "6_6") (pintype "passive"))
      (node (ref "X1") (pin "7") (pinfunction "7_7") (pintype "passive"))
      (node (ref "X1") (pin "8") (pinfunction "8_8") (pintype "passive"))
      (node (ref "X1") (pin "9") (pinfunction "9_9") (pintype "passive"))
    )
    (net (code "87") (name "Net-(DZ1A-A)") (class "Default")
      (node (ref "DZ1") (pin "1") (pinfunction "A_1") (pintype "passive"))
      (node (ref "U1") (pin "143") (pinfunction "112_I/O_143") (pintype "bidirectional"))
    )
    (net (code "88") (name "Net-(DZ1A-C)") (class "Default")
      (node (ref "DZ1") (pin "20") (pinfunction "C_20") (pintype "passive"))
      (node (ref "RN1") (pin "11") (pinfunction "11_11") (pintype "passive"))
    )
    (net (code "89") (name "Net-(DZ1B-A)") (class "Default")
      (node (ref "DZ1") (pin "10") (pinfunction "A_10") (pintype "passive"))
      (node (ref "U1") (pin "133") (pinfunction "103_I/O_133") (pintype "bidirectional"))
    )
    (net (code "90") (name "Net-(DZ1B-C)") (class "Default")
      (node (ref "DZ1") (pin "11") (pinfunction "C_11") (pintype "passive"))
      (node (ref "RN1") (pin "2") (pinfunction "2_2") (pintype "passive"))
    )
    (net (code "91") (name "Net-(DZ1C-A)") (class "Default")
      (node (ref "DZ1") (pin "2") (pinfunction "A_2") (pintype "passive"))
      (node (ref "U1") (pin "142") (pinfunction "111_I/O_142") (pintype "bidirectional"))
    )
    (net (code "92") (name "Net-(DZ1C-C)") (class "Default")
      (node (ref "DZ1") (pin "19") (pinfunction "C_19") (pintype "passive"))
      (node (ref "RN1") (pin "10") (pinfunction "10_10") (pintype "passive"))
    )
    (net (code "93") (name "Net-(DZ1D-A)") (class "Default")
      (node (ref "DZ1") (pin "3") (pinfunction "A_3") (pintype "passive"))
      (node (ref "U1") (pin "141") (pinfunction "110_I/O_141") (pintype "bidirectional"))
    )
    (net (code "94") (name "Net-(DZ1D-C)") (class "Default")
      (node (ref "DZ1") (pin "18") (pinfunction "C_18") (pintype "passive"))
      (node (ref "RN1") (pin "9") (pinfunction "9_9") (pintype "passive"))
    )
    (net (code "95") (name "Net-(DZ1E-A)") (class "Default")
      (node (ref "DZ1") (pin "4") (pinfunction "A_4") (pintype "passive"))
      (node (ref "U1") (pin "140") (pinfunction "109_I/O_140") (pintype "bidirectional"))
    )
    (net (code "96") (name "Net-(DZ1E-C)") (class "Default")
      (node (ref "DZ1") (pin "17") (pinfunction "C_17") (pintype "passive"))
      (node (ref "RN1") (pin "8") (pinfunction "8_8") (pintype "passive"))
    )
    (net (code "97") (name "Net-(DZ1F-A)") (class "Default")
      (node (ref "DZ1") (pin "5") (pinfunction "A_5") (pintype "passive"))
      (node (ref "U1") (pin "139") (pinfunction "108_I/O_139") (pintype "bidirectional"))
    )
    (net (code "98") (name "Net-(DZ1F-C)") (class "Default")
      (node (ref "DZ1") (pin "16") (pinfunction "C_16") (pintype "passive"))
      (node (ref "RN1") (pin "7") (pinfunction "7_7") (pintype "passive"))
    )
    (net (code "99") (name "Net-(DZ1G-A)") (class "Default")
      (node (ref "DZ1") (pin "6") (pinfunction "A_6") (pintype "passive"))
      (node (ref "U1") (pin "138") (pinfunction "107_I/O_138") (pintype "bidirectional"))
    )
    (net (code "100") (name "Net-(DZ1G-C)") (class "Default")
      (node (ref "DZ1") (pin "15") (pinfunction "C_15") (pintype "passive"))
      (node (ref "RN1") (pin "6") (pinfunction "6_6") (pintype "passive"))
    )
    (net (code "101") (name "Net-(DZ1H-A)") (class "Default")
      (node (ref "DZ1") (pin "7") (pinfunction "A_7") (pintype "passive"))
      (node (ref "U1") (pin "137") (pinfunction "106_I/O_137") (pintype "bidirectional"))
    )
    (net (code "102") (name "Net-(DZ1H-C)") (class "Default")
      (node (ref "DZ1") (pin "14") (pinfunction "C_14") (pintype "passive"))
      (node (ref "RN1") (pin "5") (pinfunction "5_5") (pintype "passive"))
    )
    (net (code "103") (name "Net-(DZ1I-A)") (class "Default")
      (node (ref "DZ1") (pin "8") (pinfunction "A_8") (pintype "passive"))
      (node (ref "U1") (pin "136") (pinfunction "105_I/O_136") (pintype "bidirectional"))
    )
    (net (code "104") (name "Net-(DZ1I-C)") (class "Default")
      (node (ref "DZ1") (pin "13") (pinfunction "C_13") (pintype "passive"))
      (node (ref "RN1") (pin "4") (pinfunction "4_4") (pintype "passive"))
    )
    (net (code "105") (name "Net-(DZ1J-A)") (class "Default")
      (node (ref "DZ1") (pin "9") (pinfunction "A_9") (pintype "passive"))
      (node (ref "U1") (pin "134") (pinfunction "104_I/O_134") (pintype "bidirectional"))
    )
    (net (code "106") (name "Net-(DZ1J-C)") (class "Default")
      (node (ref "DZ1") (pin "12") (pinfunction "C_12") (pintype "passive"))
      (node (ref "RN1") (pin "3") (pinfunction "3_3") (pintype "passive"))
    )
    (net (code "107") (name "Net-(LED1-C)") (class "Default")
      (node (ref "LED1") (pin "K") (pinfunction "C_K") (pintype "passive"))
      (node (ref "R17") (pin "1") (pinfunction "1_1") (pintype "passive"))
    )
    (net (code "108") (name "Net-(LED2-C)") (class "Default")
      (node (ref "LED2") (pin "K") (pinfunction "C_K") (pintype "passive"))
      (node (ref "R14") (pin "1") (pinfunction "1_1") (pintype "passive"))
    )
    (net (code "109") (name "Net-(LED3-C)") (class "Default")
      (node (ref "LED3") (pin "K") (pinfunction "C_K") (pintype "passive"))
      (node (ref "R15") (pin "1") (pinfunction "1_1") (pintype "passive"))
    )
    (net (code "110") (name "Net-(LED4-C)") (class "Default")
      (node (ref "LED4") (pin "K") (pinfunction "C_K") (pintype "passive"))
      (node (ref "R16") (pin "1") (pinfunction "1_1") (pintype "passive"))
    )
    (net (code "111") (name "Net-(S1A-2)") (class "Default")
      (node (ref "S1") (pin "16") (pinfunction "2_16") (pintype "passive"))
      (node (ref "U1") (pin "74") (pinfunction "60_I/O_74") (pintype "bidirectional"))
    )
    (net (code "112") (name "Net-(S1B-2)") (class "Default")
      (node (ref "S1") (pin "15") (pinfunction "2_15") (pintype "passive"))
      (node (ref "U1") (pin "75") (pinfunction "61_I/O_75") (pintype "bidirectional"))
    )
    (net (code "113") (name "Net-(S1C-2)") (class "Default")
      (node (ref "S1") (pin "14") (pinfunction "2_14") (pintype "passive"))
      (node (ref "U1") (pin "78") (pinfunction "62_I/O_78") (pintype "bidirectional"))
    )
    (net (code "114") (name "Net-(S1D-2)") (class "Default")
      (node (ref "S1") (pin "13") (pinfunction "2_13") (pintype "passive"))
      (node (ref "U1") (pin "79") (pinfunction "63_I/O_79") (pintype "bidirectional"))
    )
    (net (code "115") (name "Net-(S1E-2)") (class "Default")
      (node (ref "S1") (pin "12") (pinfunction "2_12") (pintype "passive"))
      (node (ref "U1") (pin "80") (pinfunction "64_I/O_80") (pintype "bidirectional"))
    )
    (net (code "116") (name "Net-(S1F-2)") (class "Default")
      (node (ref "S1") (pin "11") (pinfunction "2_11") (pintype "passive"))
      (node (ref "U1") (pin "81") (pinfunction "65_I/O_81") (pintype "bidirectional"))
    )
    (net (code "117") (name "Net-(S1G-2)") (class "Default")
      (node (ref "S1") (pin "10") (pinfunction "2_10") (pintype "passive"))
      (node (ref "U1") (pin "82") (pinfunction "66_I/O_82") (pintype "bidirectional"))
    )
    (net (code "118") (name "Net-(S1H-2)") (class "Default")
      (node (ref "S1") (pin "9") (pinfunction "2_9") (pintype "passive"))
      (node (ref "U1") (pin "83") (pinfunction "67_I/O_83") (pintype "bidirectional"))
    )
    (net (code "119") (name "Net-(U1D-68_I{slash}O)") (class "Default")
      (node (ref "JP2") (pin "8") (pinfunction "8_8") (pintype "passive"))
      (node (ref "U1") (pin "84") (pinfunction "68_I/O_84") (pintype "bidirectional"))
    )
    (net (code "120") (name "Net-(U1D-69_I{slash}O)") (class "Default")
      (node (ref "JP2") (pin "7") (pinfunction "7_7") (pintype "passive"))
      (node (ref "U1") (pin "86") (pinfunction "69_I/O_86") (pintype "bidirectional"))
    )
    (net (code "121") (name "Net-(U1D-71_I{slash}O)") (class "Default")
      (node (ref "JP2") (pin "6") (pinfunction "6_6") (pintype "passive"))
      (node (ref "U1") (pin "87") (pinfunction "71_I/O_87") (pintype "bidirectional"))
    )
    (net (code "122") (name "Net-(U1D-72_I{slash}O)") (class "Default")
      (node (ref "JP2") (pin "5") (pinfunction "5_5") (pintype "passive"))
      (node (ref "U1") (pin "88") (pinfunction "72_I/O_88") (pintype "bidirectional"))
    )
    (net (code "123") (name "Net-(U1D-73_I{slash}O)") (class "Default")
      (node (ref "JP2") (pin "4") (pinfunction "4_4") (pintype "passive"))
      (node (ref "U1") (pin "90") (pinfunction "73_I/O_90") (pintype "bidirectional"))
    )
    (net (code "124") (name "Net-(U1D-74_I{slash}O)") (class "Default")
      (node (ref "JP2") (pin "3") (pinfunction "3_3") (pintype "passive"))
      (node (ref "U1") (pin "91") (pinfunction "74_I/O_91") (pintype "bidirectional"))
    )
    (net (code "125") (name "Net-(U1D-75_I{slash}O)") (class "Default")
      (node (ref "JP2") (pin "2") (pinfunction "2_2") (pintype "passive"))
      (node (ref "U1") (pin "92") (pinfunction "75_I/O_92") (pintype "bidirectional"))
    )
    (net (code "126") (name "Net-(U1D-76_I{slash}O)") (class "Default")
      (node (ref "JP2") (pin "1") (pinfunction "1_1") (pintype "passive"))
      (node (ref "U1") (pin "93") (pinfunction "76_I/O_93") (pintype "bidirectional"))
    )
    (net (code "127") (name "Net-(U1D-77_I{slash}O)") (class "Default")
      (node (ref "JP4") (pin "8") (pinfunction "8_8") (pintype "passive"))
      (node (ref "U1") (pin "96") (pinfunction "77_I/O_96") (pintype "bidirectional"))
    )
    (net (code "128") (name "Net-(U1D-78_I{slash}O)") (class "Default")
      (node (ref "JP4") (pin "7") (pinfunction "7_7") (pintype "passive"))
      (node (ref "U1") (pin "97") (pinfunction "78_I/O_97") (pintype "bidirectional"))
    )
    (net (code "129") (name "Net-(U1D-79_I{slash}O)") (class "Default")
      (node (ref "JP4") (pin "6") (pinfunction "6_6") (pintype "passive"))
      (node (ref "U1") (pin "98") (pinfunction "79_I/O_98") (pintype "bidirectional"))
    )
    (net (code "130") (name "Net-(U1D-80_I{slash}O)") (class "Default")
      (node (ref "JP4") (pin "5") (pinfunction "5_5") (pintype "passive"))
      (node (ref "U1") (pin "99") (pinfunction "80_I/O_99") (pintype "bidirectional"))
    )
    (net (code "131") (name "Net-(U1D-81_I{slash}O)") (class "Default")
      (node (ref "JP4") (pin "4") (pinfunction "4_4") (pintype "passive"))
      (node (ref "U1") (pin "100") (pinfunction "81_I/O_100") (pintype "bidirectional"))
    )
    (net (code "132") (name "Net-(U1D-82_I{slash}O)") (class "Default")
      (node (ref "JP4") (pin "3") (pinfunction "3_3") (pintype "passive"))
      (node (ref "U1") (pin "101") (pinfunction "82_I/O_101") (pintype "bidirectional"))
    )
    (net (code "133") (name "Net-(U1D-83_I{slash}O)") (class "Default")
      (node (ref "JP4") (pin "2") (pinfunction "2_2") (pintype "passive"))
      (node (ref "U1") (pin "102") (pinfunction "83_I/O_102") (pintype "bidirectional"))
    )
    (net (code "134") (name "Net-(U1D-84_I{slash}O)") (class "Default")
      (node (ref "JP4") (pin "1") (pinfunction "1_1") (pintype "passive"))
      (node (ref "U1") (pin "103") (pinfunction "84_I/O_103") (pintype "bidirectional"))
    )
    (net (code "135") (name "Net-(U1D-88_I{slash}O)") (class "Default")
      (node (ref "R1") (pin "1") (pinfunction "1_1") (pintype "passive"))
      (node (ref "U1") (pin "108") (pinfunction "88_I/O_108") (pintype "bidirectional"))
    )
    (net (code "136") (name "Net-(U1D-89_I{slash}O)") (class "Default")
      (node (ref "R2") (pin "1") (pinfunction "1_1") (pintype "passive"))
      (node (ref "U1") (pin "109") (pinfunction "89_I/O_109") (pintype "bidirectional"))
    )
    (net (code "137") (name "Net-(U1D-90_I{slash}O)") (class "Default")
      (node (ref "R3") (pin "1") (pinfunction "1_1") (pintype "passive"))
      (node (ref "U1") (pin "110") (pinfunction "90_I/O_110") (pintype "bidirectional"))
    )
    (net (code "138") (name "Net-(U1D-91_I{slash}O)") (class "Default")
      (node (ref "R4") (pin "1") (pinfunction "1_1") (pintype "passive"))
      (node (ref "U1") (pin "111") (pinfunction "91_I/O_111") (pintype "bidirectional"))
    )
    (net (code "139") (name "Net-(U1D-92_I{slash}O)") (class "Default")
      (node (ref "R5") (pin "1") (pinfunction "1_1") (pintype "passive"))
      (node (ref "U1") (pin "112") (pinfunction "92_I/O_112") (pintype "bidirectional"))
    )
    (net (code "140") (name "Net-(U1D-93_I{slash}O)") (class "Default")
      (node (ref "R6") (pin "1") (pinfunction "1_1") (pintype "passive"))
      (node (ref "U1") (pin "113") (pinfunction "93_I/O_113") (pintype "bidirectional"))
    )
    (net (code "141") (name "Net-(U1D-94_I{slash}O)") (class "Default")
      (node (ref "R7") (pin "1") (pinfunction "1_1") (pintype "passive"))
      (node (ref "U1") (pin "116") (pinfunction "94_I/O_116") (pintype "bidirectional"))
    )
    (net (code "142") (name "Net-(U1D-95_I{slash}O)") (class "Default")
      (node (ref "R8") (pin "1") (pinfunction "1_1") (pintype "passive"))
      (node (ref "U1") (pin "117") (pinfunction "95_I/O_117") (pintype "bidirectional"))
    )
    (net (code "143") (name "Net-(U1D-96_I{slash}O)") (class "Default")
      (node (ref "R9") (pin "1") (pinfunction "1_1") (pintype "passive"))
      (node (ref "U1") (pin "118") (pinfunction "96_I/O_118") (pintype "bidirectional"))
    )
    (net (code "144") (name "Net-(U1D-99_I{slash}O)") (class "Default")
      (node (ref "LED4") (pin "A") (pinfunction "A_A") (pintype "passive"))
      (node (ref "U1") (pin "121") (pinfunction "99_I/O_121") (pintype "bidirectional"))
    )
    (net (code "145") (name "Net-(U1D-100_I{slash}O)") (class "Default")
      (node (ref "LED3") (pin "A") (pinfunction "A_A") (pintype "passive"))
      (node (ref "U1") (pin "122") (pinfunction "100_I/O_122") (pintype "bidirectional"))
    )
    (net (code "146") (name "Net-(U1D-101_I{slash}O)") (class "Default")
      (node (ref "LED2") (pin "A") (pinfunction "A_A") (pintype "passive"))
      (node (ref "U1") (pin "131") (pinfunction "101_I/O_131") (pintype "bidirectional"))
    )
    (net (code "147") (name "Net-(U1D-102_I{slash}O)") (class "Default")
      (node (ref "LED1") (pin "A") (pinfunction "A_A") (pintype "passive"))
      (node (ref "U1") (pin "132") (pinfunction "102_I/O_132") (pintype "bidirectional"))
    )
    (net (code "148") (name "unconnected-(JP3-Pad4)") (class "Default")
      (node (ref "JP3") (pin "4") (pinfunction "4_4") (pintype "passive"))
    )
    (net (code "149") (name "unconnected-(JP3-Pad5)") (class "Default")
      (node (ref "JP3") (pin "5") (pinfunction "5_5") (pintype "passive"))
    )
    (net (code "150") (name "unconnected-(QG2-E{slash}D-Pad1)") (class "Default")
      (node (ref "QG2") (pin "1") (pinfunction "E/D_1") (pintype "input"))
    )
    (net (code "151") (name "unconnected-(ST1A-P-PadB9)") (class "Default")
      (node (ref "ST1") (pin "B9") (pinfunction "P_B9") (pintype "bidirectional"))
    )
    (net (code "152") (name "unconnected-(ST1AA-P-PadB16)") (class "Default")
      (node (ref "ST1") (pin "B16") (pinfunction "P_B16") (pintype "bidirectional"))
    )
    (net (code "153") (name "unconnected-(ST1AB-P-PadB17)") (class "Default")
      (node (ref "ST1") (pin "B17") (pinfunction "P_B17") (pintype "bidirectional"))
    )
    (net (code "154") (name "unconnected-(ST1AC-P-PadB18)") (class "Default")
      (node (ref "ST1") (pin "B18") (pinfunction "P_B18") (pintype "bidirectional"))
    )
    (net (code "155") (name "unconnected-(ST1AD-P-PadB26)") (class "Default")
      (node (ref "ST1") (pin "B26") (pinfunction "P_B26") (pintype "bidirectional"))
    )
    (net (code "156") (name "unconnected-(ST1AE-P-PadB27)") (class "Default")
      (node (ref "ST1") (pin "B27") (pinfunction "P_B27") (pintype "bidirectional"))
    )
    (net (code "157") (name "unconnected-(ST1AF-P-PadB28)") (class "Default")
      (node (ref "ST1") (pin "B28") (pinfunction "P_B28") (pintype "bidirectional"))
    )
    (net (code "158") (name "unconnected-(ST1AG-P-PadB4)") (class "Default")
      (node (ref "ST1") (pin "B4") (pinfunction "P_B4") (pintype "bidirectional"))
    )
    (net (code "159") (name "unconnected-(ST1AH-P-PadB5)") (class "Default")
      (node (ref "ST1") (pin "B5") (pinfunction "P_B5") (pintype "bidirectional"))
    )
    (net (code "160") (name "unconnected-(ST1AI-P-PadB6)") (class "Default")
      (node (ref "ST1") (pin "B6") (pinfunction "P_B6") (pintype "bidirectional"))
    )
    (net (code "161") (name "unconnected-(ST1AJ-P-PadB8)") (class "Default")
      (node (ref "ST1") (pin "B8") (pinfunction "P_B8") (pintype "bidirectional"))
    )
    (net (code "162") (name "unconnected-(ST1AK-P-PadA11)") (class "Default")
      (node (ref "ST1") (pin "A11") (pinfunction "P_A11") (pintype "bidirectional"))
    )
    (net (code "163") (name "unconnected-(ST1AW-P-PadA10)") (class "Default")
      (node (ref "ST1") (pin "A10") (pinfunction "P_A10") (pintype "bidirectional"))
    )
    (net (code "164") (name "unconnected-(ST1Y-P-PadB10)") (class "Default")
      (node (ref "ST1") (pin "B10") (pinfunction "P_B10") (pintype "bidirectional"))
    )
    (net (code "165") (name "unconnected-(ST1Z-P-PadB15)") (class "Default")
      (node (ref "ST1") (pin "B15") (pinfunction "P_B15") (pintype "bidirectional"))
    )
    (net (code "166") (name "unconnected-(U$2-NC-Pad1)") (class "Default")
      (node (ref "U$2") (pin "1") (pinfunction "NC_1") (pintype "bidirectional"))
    )
    (net (code "167") (name "unconnected-(U1-Pad37)") (class "Default")
      (node (ref "U1") (pin "37") (pinfunction "37_37") (pintype "bidirectional"))
    )
    (net (code "168") (name "unconnected-(U1B-2_INPUT{slash}OE1-Pad126)") (class "Default")
      (node (ref "U1") (pin "126") (pinfunction "2_INPUT/OE1_126") (pintype "input"))
    )
    (net (code "169") (name "unconnected-(U1B-3_INPUT{slash}~{GCLR}-Pad127)") (class "Default")
      (node (ref "U1") (pin "127") (pinfunction "3_INPUT/~{GCLR}_127") (pintype "input"))
    )
    (net (code "170") (name "unconnected-(X1-Pad4)") (class "Default")
      (node (ref "X1") (pin "4") (pinfunction "4_4") (pintype "passive"))
    )
    (net (code "171") (name "unconnected-(X1-Pad11)") (class "Default")
      (node (ref "X1") (pin "11") (pinfunction "11_11") (pintype "passive"))
    )
    (net (code "172") (name "unconnected-(X1-Pad12)") (class "Default")
      (node (ref "X1") (pin "12") (pinfunction "12_12") (pintype "passive"))
    )
    (net (code "173") (name "unconnected-(X1-Pad15)") (class "Default")
      (node (ref "X1") (pin "15") (pinfunction "15_15") (pintype "passive"))
    )
  )
)
